# M-Knob.net
KiCad netlist of a schematic drawn in EAGLE
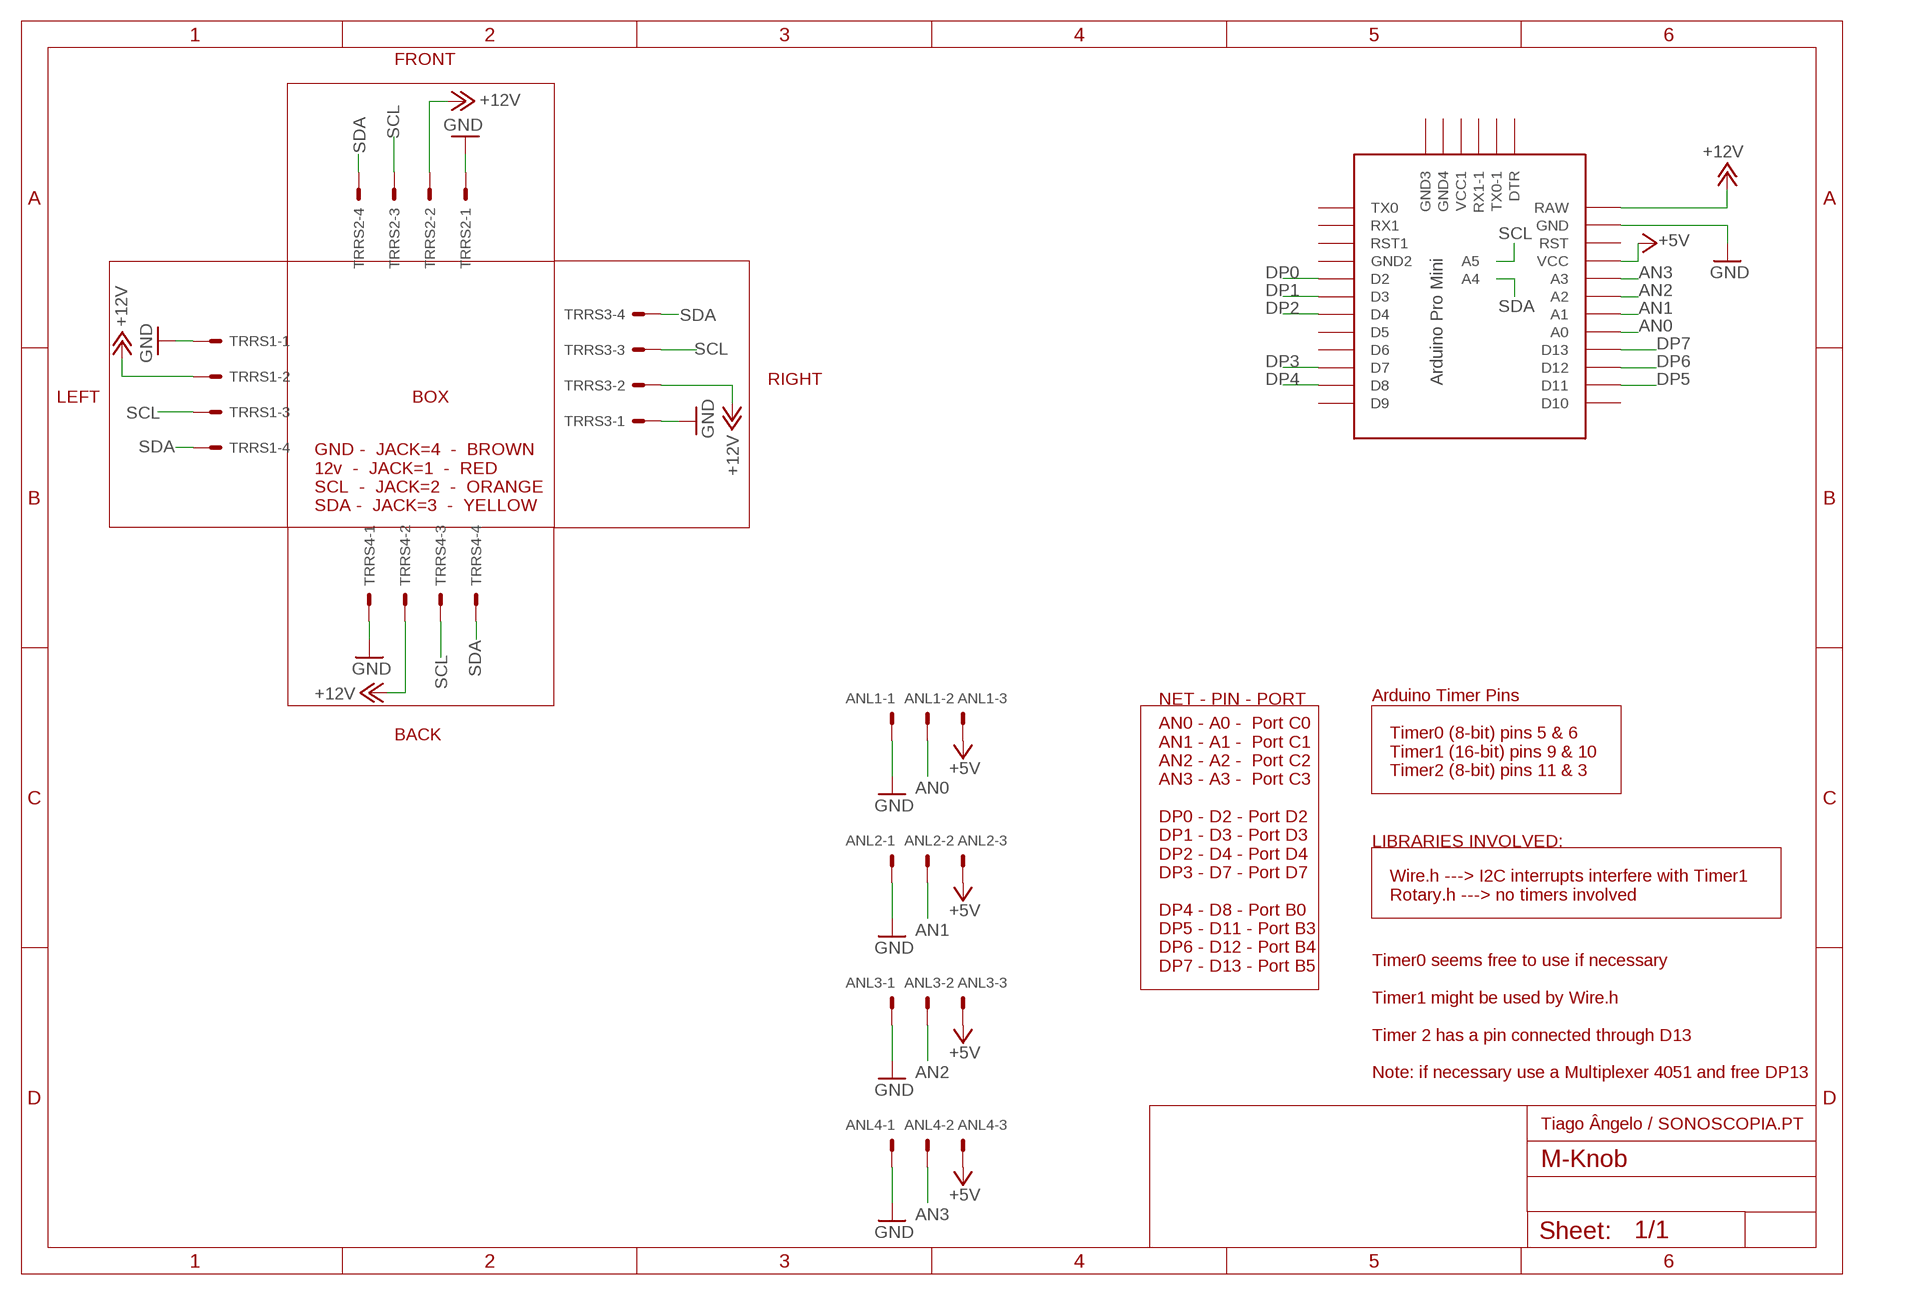
[diagram p0: schematic, sheet 1]

(export (version "E")
  (design (tool "Eeschema 10.0.6"))
  (components
    (comp (ref "ANL1")
      (value "22-27-2031-03")
      (footprint "eagle-import:6410-03")
      (libsource (lib "eagle-import") (part "22-?-0327-2031"))
    )
    (comp (ref "ANL2")
      (value "22-27-2031-03")
      (footprint "eagle-import:6410-03")
      (libsource (lib "eagle-import") (part "22-?-0327-2031"))
    )
    (comp (ref "ANL3")
      (value "22-27-2031-03")
      (footprint "eagle-import:6410-03")
      (libsource (lib "eagle-import") (part "22-?-0327-2031"))
    )
    (comp (ref "ANL4")
      (value "22-27-2031-03")
      (footprint "eagle-import:6410-03")
      (libsource (lib "eagle-import") (part "22-?-0327-2031"))
    )
    (comp (ref "TRRS1")
      (value "22-27-2041-04")
      (footprint "eagle-import:6410-04")
      (libsource (lib "eagle-import") (part "22-?-0427-2041"))
    )
    (comp (ref "TRRS2")
      (value "22-27-2041-04")
      (footprint "eagle-import:6410-04")
      (libsource (lib "eagle-import") (part "22-?-0427-2041"))
    )
    (comp (ref "TRRS3")
      (value "22-27-2041-04")
      (footprint "eagle-import:6410-04")
      (libsource (lib "eagle-import") (part "22-?-0427-2041"))
    )
    (comp (ref "TRRS4")
      (value "22-27-2041-04")
      (footprint "eagle-import:6410-04")
      (libsource (lib "eagle-import") (part "22-?-0427-2041"))
    )
    (comp (ref "U$1")
      (value "PRO-MINI-2")
      (footprint "eagle-import:PRO-MINI-2")
      (libsource (lib "eagle-import") (part "PRO-MINI-2"))
    )
  )
  (nets
    (net (code "1") (name "+5V") (class "Default")
      (node (ref "ANL1") (pin "3") (pinfunction "S_3") (pintype "passive"))
      (node (ref "ANL2") (pin "3") (pinfunction "S_3") (pintype "passive"))
      (node (ref "ANL3") (pin "3") (pinfunction "S_3") (pintype "passive"))
      (node (ref "ANL4") (pin "3") (pinfunction "S_3") (pintype "passive"))
      (node (ref "U$1") (pin "VCC") (pinfunction "VCC_VCC") (pintype "bidirectional"))
    )
    (net (code "2") (name "+12V") (class "Default")
      (node (ref "TRRS1") (pin "2") (pinfunction "S_2") (pintype "passive"))
      (node (ref "TRRS2") (pin "2") (pinfunction "S_2") (pintype "passive"))
      (node (ref "TRRS3") (pin "2") (pinfunction "S_2") (pintype "passive"))
      (node (ref "TRRS4") (pin "2") (pinfunction "S_2") (pintype "passive"))
      (node (ref "U$1") (pin "RAW") (pinfunction "RAW_RAW") (pintype "bidirectional"))
    )
    (net (code "3") (name "/AN0") (class "Default")
      (node (ref "ANL1") (pin "2") (pinfunction "S_2") (pintype "passive"))
      (node (ref "U$1") (pin "A0") (pinfunction "A0_A0") (pintype "bidirectional"))
    )
    (net (code "4") (name "/AN1") (class "Default")
      (node (ref "ANL2") (pin "2") (pinfunction "S_2") (pintype "passive"))
      (node (ref "U$1") (pin "A1") (pinfunction "A1_A1") (pintype "bidirectional"))
    )
    (net (code "5") (name "/AN2") (class "Default")
      (node (ref "ANL3") (pin "2") (pinfunction "S_2") (pintype "passive"))
      (node (ref "U$1") (pin "A2") (pinfunction "A2_A2") (pintype "bidirectional"))
    )
    (net (code "6") (name "/AN3") (class "Default")
      (node (ref "ANL4") (pin "2") (pinfunction "S_2") (pintype "passive"))
      (node (ref "U$1") (pin "A3") (pinfunction "A3_A3") (pintype "bidirectional"))
    )
    (net (code "7") (name "/DP0") (class "Default")
      (node (ref "U$1") (pin "D2") (pinfunction "D2_D2") (pintype "bidirectional"))
    )
    (net (code "8") (name "/DP1") (class "Default")
      (node (ref "U$1") (pin "D3") (pinfunction "D3_D3") (pintype "bidirectional"))
    )
    (net (code "9") (name "/DP2") (class "Default")
      (node (ref "U$1") (pin "D4") (pinfunction "D4_D4") (pintype "bidirectional"))
    )
    (net (code "10") (name "/DP3") (class "Default")
      (node (ref "U$1") (pin "D7") (pinfunction "D7_D7") (pintype "bidirectional"))
    )
    (net (code "11") (name "/DP4") (class "Default")
      (node (ref "U$1") (pin "D8") (pinfunction "D8_D8") (pintype "bidirectional"))
    )
    (net (code "12") (name "/DP5") (class "Default")
      (node (ref "U$1") (pin "D11") (pinfunction "D11_D11") (pintype "bidirectional"))
    )
    (net (code "13") (name "/DP6") (class "Default")
      (node (ref "U$1") (pin "D12") (pinfunction "D12_D12") (pintype "bidirectional"))
    )
    (net (code "14") (name "/DP7") (class "Default")
      (node (ref "U$1") (pin "D13") (pinfunction "D13_D13") (pintype "bidirectional"))
    )
    (net (code "15") (name "/SCL") (class "Default")
      (node (ref "TRRS1") (pin "3") (pinfunction "S_3") (pintype "passive"))
      (node (ref "TRRS2") (pin "3") (pinfunction "S_3") (pintype "passive"))
      (node (ref "TRRS3") (pin "3") (pinfunction "S_3") (pintype "passive"))
      (node (ref "TRRS4") (pin "3") (pinfunction "S_3") (pintype "passive"))
      (node (ref "U$1") (pin "A5") (pinfunction "A5_A5") (pintype "bidirectional"))
    )
    (net (code "16") (name "/SDA") (class "Default")
      (node (ref "TRRS1") (pin "4") (pinfunction "S_4") (pintype "passive"))
      (node (ref "TRRS2") (pin "4") (pinfunction "S_4") (pintype "passive"))
      (node (ref "TRRS3") (pin "4") (pinfunction "S_4") (pintype "passive"))
      (node (ref "TRRS4") (pin "4") (pinfunction "S_4") (pintype "passive"))
      (node (ref "U$1") (pin "A4") (pinfunction "A4_A4") (pintype "bidirectional"))
    )
    (net (code "17") (name "GND") (class "Default")
      (node (ref "ANL1") (pin "1") (pinfunction "S_1") (pintype "passive"))
      (node (ref "ANL2") (pin "1") (pinfunction "S_1") (pintype "passive"))
      (node (ref "ANL3") (pin "1") (pinfunction "S_1") (pintype "passive"))
      (node (ref "ANL4") (pin "1") (pinfunction "S_1") (pintype "passive"))
      (node (ref "TRRS1") (pin "1") (pinfunction "S_1") (pintype "passive"))
      (node (ref "TRRS2") (pin "1") (pinfunction "S_1") (pintype "passive"))
      (node (ref "TRRS3") (pin "1") (pinfunction "S_1") (pintype "passive"))
      (node (ref "TRRS4") (pin "1") (pinfunction "S_1") (pintype "passive"))
      (node (ref "U$1") (pin "GND") (pinfunction "GND_GND") (pintype "bidirectional"))
    )
    (net (code "18") (name "unconnected-(U$1-GND2-PadGND1)") (class "Default")
      (node (ref "U$1") (pin "GND1") (pinfunction "GND2_GND1") (pintype "bidirectional"))
    )
    (net (code "19") (name "unconnected-(U$1-GND3-PadGND2)") (class "Default")
      (node (ref "U$1") (pin "GND2") (pinfunction "GND3_GND2") (pintype "bidirectional"))
    )
    (net (code "20") (name "unconnected-(U$1-GND4-PadGND3)") (class "Default")
      (node (ref "U$1") (pin "GND3") (pinfunction "GND4_GND3") (pintype "bidirectional"))
    )
    (net (code "21") (name "unconnected-(U$1-PadD5)") (class "Default")
      (node (ref "U$1") (pin "D5") (pinfunction "D5_D5") (pintype "bidirectional"))
    )
    (net (code "22") (name "unconnected-(U$1-PadD6)") (class "Default")
      (node (ref "U$1") (pin "D6") (pinfunction "D6_D6") (pintype "bidirectional"))
    )
    (net (code "23") (name "unconnected-(U$1-PadD9)") (class "Default")
      (node (ref "U$1") (pin "D9") (pinfunction "D9_D9") (pintype "bidirectional"))
    )
    (net (code "24") (name "unconnected-(U$1-PadD10)") (class "Default")
      (node (ref "U$1") (pin "D10") (pinfunction "D10_D10") (pintype "bidirectional"))
    )
    (net (code "25") (name "unconnected-(U$1-PadDTR)") (class "Default")
      (node (ref "U$1") (pin "DTR") (pinfunction "DTR_DTR") (pintype "bidirectional"))
    )
    (net (code "26") (name "unconnected-(U$1-PadRST)") (class "Default")
      (node (ref "U$1") (pin "RST") (pinfunction "RST_RST") (pintype "bidirectional"))
    )
    (net (code "27") (name "unconnected-(U$1-PadRST1)") (class "Default")
      (node (ref "U$1") (pin "RST1") (pinfunction "RST1_RST1") (pintype "bidirectional"))
    )
    (net (code "28") (name "unconnected-(U$1-PadRX1)") (class "Default")
      (node (ref "U$1") (pin "RX1") (pinfunction "RX1_RX1") (pintype "bidirectional"))
    )
    (net (code "29") (name "unconnected-(U$1-PadRX1-1)") (class "Default")
      (node (ref "U$1") (pin "RX1-1") (pinfunction "RX1-1_RX1-1") (pintype "bidirectional"))
    )
    (net (code "30") (name "unconnected-(U$1-PadTX0)") (class "Default")
      (node (ref "U$1") (pin "TX0") (pinfunction "TX0_TX0") (pintype "bidirectional"))
    )
    (net (code "31") (name "unconnected-(U$1-PadTX0-1)") (class "Default")
      (node (ref "U$1") (pin "TX0-1") (pinfunction "TX0-1_TX0-1") (pintype "bidirectional"))
    )
    (net (code "32") (name "unconnected-(U$1-PadVCC1)") (class "Default")
      (node (ref "U$1") (pin "VCC1") (pinfunction "VCC1_VCC1") (pintype "bidirectional"))
    )
  )
)
